# Arduino-Pro-v16.net
KiCad netlist of a schematic drawn in EAGLE
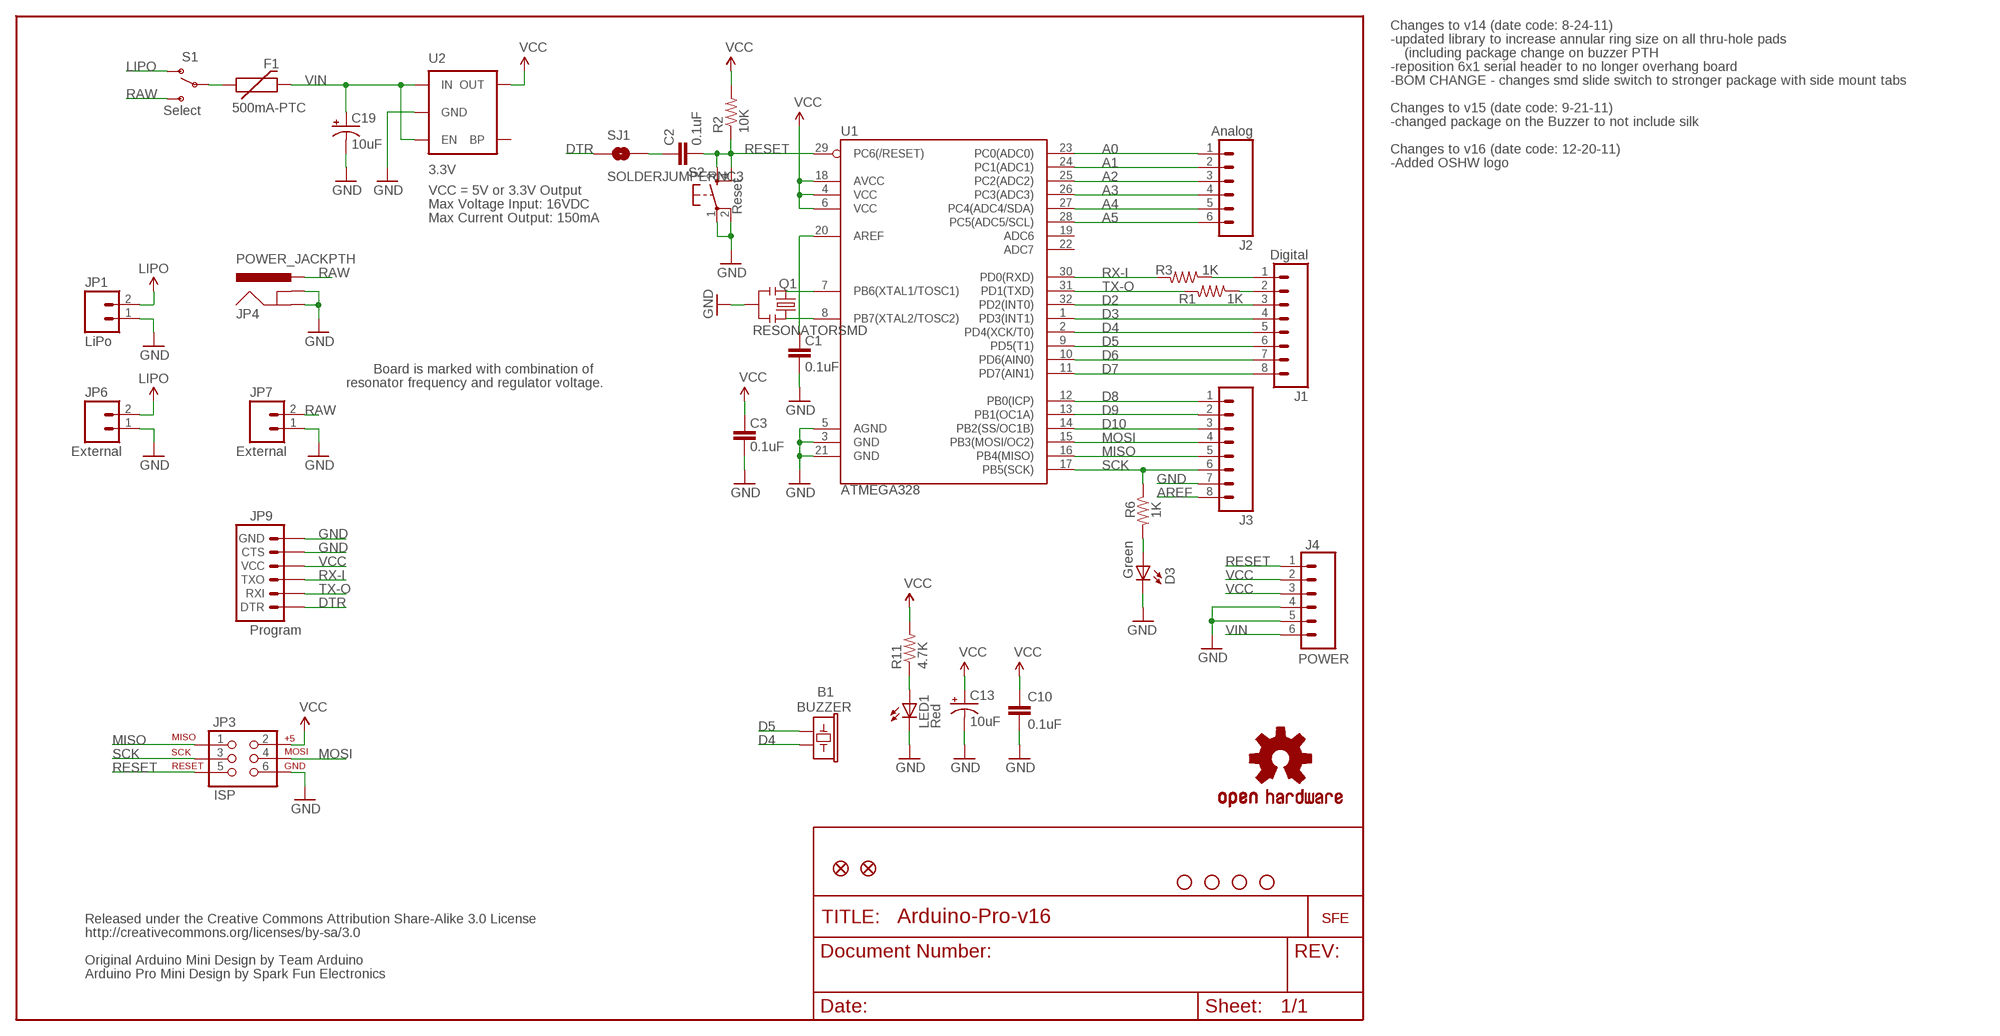
[diagram p0: schematic, sheet 1]

(export (version "E")
  (design (tool "Eeschema 10.0.6"))
  (components
    (comp (ref "B1")
      (value "BUZZER")
      (footprint "eagle-import:BUZZER-12MM-NS-KIT")
      (libsource (lib "eagle-import") (part "BUZZERPTH-NS-KIT"))
    )
    (comp (ref "C1")
      (value "0.1uF")
      (footprint "eagle-import:0402-CAP")
      (libsource (lib "eagle-import") (part "CAP0402-CAP"))
    )
    (comp (ref "C2")
      (value "0.1uF")
      (footprint "eagle-import:0402-CAP")
      (libsource (lib "eagle-import") (part "CAP0402-CAP"))
    )
    (comp (ref "C3")
      (value "0.1uF")
      (footprint "eagle-import:0402-CAP")
      (libsource (lib "eagle-import") (part "CAP0402-CAP"))
    )
    (comp (ref "C10")
      (value "0.1uF")
      (footprint "eagle-import:0402-CAP")
      (libsource (lib "eagle-import") (part "CAP0402-CAP"))
    )
    (comp (ref "C13")
      (value "10uF")
      (footprint "eagle-import:EIA3216")
      (libsource (lib "eagle-import") (part "CAP_POL1206"))
    )
    (comp (ref "C19")
      (value "10uF")
      (footprint "eagle-import:EIA3216")
      (libsource (lib "eagle-import") (part "CAP_POL1206"))
    )
    (comp (ref "D3")
      (value "Green")
      (footprint "eagle-import:LED-0603")
      (libsource (lib "eagle-import") (part "LED0603"))
    )
    (comp (ref "F1")
      (value "500mA-PTC")
      (footprint "eagle-import:PTC-1206")
      (libsource (lib "eagle-import") (part "PTCSMD"))
    )
    (comp (ref "J1")
      (value "Digital")
      (footprint "eagle-import:1X08")
      (libsource (lib "eagle-import") (part "M081X08"))
    )
    (comp (ref "J2")
      (value "Analog")
      (footprint "eagle-import:1X06")
      (libsource (lib "eagle-import") (part "M06SIP"))
    )
    (comp (ref "J3")
      (value "M081X08")
      (footprint "eagle-import:1X08")
      (libsource (lib "eagle-import") (part "M081X08"))
    )
    (comp (ref "J4")
      (value "POWER")
      (footprint "eagle-import:1X06")
      (libsource (lib "eagle-import") (part "M06SIP"))
    )
    (comp (ref "JP1")
      (value "LiPo")
      (footprint "eagle-import:JST-2-SMD")
      (libsource (lib "eagle-import") (part "M02-JST-2MM-SMT"))
    )
    (comp (ref "JP2")
      (value "FIDUCIAL1X2.5")
      (footprint "eagle-import:FIDUCIAL-1X2.5")
      (libsource (lib "eagle-import") (part "FIDUCIAL1X2.5"))
    )
    (comp (ref "JP3")
      (value "ISP")
      (footprint "eagle-import:2X3")
      (libsource (lib "eagle-import") (part "AVR_SPI_PRG_6PTH"))
    )
    (comp (ref "JP4")
      (value "POWER_JACKPTH")
      (footprint "eagle-import:POWER_JACK_PTH")
      (libsource (lib "eagle-import") (part "POWER_JACKPTH"))
    )
    (comp (ref "JP5")
      (value "FIDUCIAL1X2.5")
      (footprint "eagle-import:FIDUCIAL-1X2.5")
      (libsource (lib "eagle-import") (part "FIDUCIAL1X2.5"))
    )
    (comp (ref "JP6")
      (value "External")
      (footprint "eagle-import:1X02")
      (libsource (lib "eagle-import") (part "M02PTH"))
    )
    (comp (ref "JP7")
      (value "External")
      (footprint "eagle-import:1X02")
      (libsource (lib "eagle-import") (part "M02PTH"))
    )
    (comp (ref "JP9")
      (value "Program")
      (footprint "eagle-import:1X06-SMD")
      (libsource (lib "eagle-import") (part "ARDUINO_SERIAL_PROGRAMSMD"))
    )
    (comp (ref "LED1")
      (value "Red")
      (footprint "eagle-import:LED-0603")
      (libsource (lib "eagle-import") (part "LED0603"))
    )
    (comp (ref "Q1")
      (value "RESONATORSMD")
      (footprint "eagle-import:RESONATOR-SMD")
      (libsource (lib "eagle-import") (part "RESONATORSMD"))
    )
    (comp (ref "R1")
      (value "1K")
      (footprint "eagle-import:0402-RES")
      (libsource (lib "eagle-import") (part "RESISTOR0402-RES"))
    )
    (comp (ref "R2")
      (value "10K")
      (footprint "eagle-import:0402-RES")
      (libsource (lib "eagle-import") (part "RESISTOR0402-RES"))
    )
    (comp (ref "R3")
      (value "1K")
      (footprint "eagle-import:0402-RES")
      (libsource (lib "eagle-import") (part "RESISTOR0402-RES"))
    )
    (comp (ref "R6")
      (value "1K")
      (footprint "eagle-import:0402-RES")
      (libsource (lib "eagle-import") (part "RESISTOR0402-RES"))
    )
    (comp (ref "R11")
      (value "4.7K")
      (footprint "eagle-import:0402-RES")
      (libsource (lib "eagle-import") (part "RESISTOR0402-RES"))
    )
    (comp (ref "S1")
      (value "Select")
      (footprint "eagle-import:SWITCH-SPST-SMD-A")
      (libsource (lib "eagle-import") (part "SWITCH-SPST-SMD-A"))
    )
    (comp (ref "S2")
      (value "Reset")
      (footprint "eagle-import:TACTILE_SWITCH_SMD")
      (libsource (lib "eagle-import") (part "TAC_SWITCHSMD"))
    )
    (comp (ref "SJ1")
      (value "SOLDERJUMPERNC3")
      (footprint "eagle-import:SJ_2S-NOTRACE")
      (libsource (lib "eagle-import") (part "SOLDERJUMPERNC2"))
    )
    (comp (ref "U$1")
      (value "STAND-OFF")
      (footprint "eagle-import:STAND-OFF")
      (libsource (lib "eagle-import") (part "STAND-OFF"))
    )
    (comp (ref "U$2")
      (value "OSHW-LOGOL")
      (footprint "eagle-import:OSHW-LOGO-L")
      (libsource (lib "eagle-import") (part "OSHW-LOGOL"))
    )
    (comp (ref "U$3")
      (value "STAND-OFF")
      (footprint "eagle-import:STAND-OFF")
      (libsource (lib "eagle-import") (part "STAND-OFF"))
    )
    (comp (ref "U$9")
      (value "STAND-OFF")
      (footprint "eagle-import:STAND-OFF")
      (libsource (lib "eagle-import") (part "STAND-OFF"))
    )
    (comp (ref "U$10")
      (value "STAND-OFF")
      (footprint "eagle-import:STAND-OFF")
      (libsource (lib "eagle-import") (part "STAND-OFF"))
    )
    (comp (ref "U$11")
      (value "LOGO-SFENEW")
      (footprint "eagle-import:SFE-NEW-WEBLOGO")
      (libsource (lib "eagle-import") (part "LOGO-SFENEW"))
    )
    (comp (ref "U1")
      (value "ATMEGA328")
      (footprint "eagle-import:TQFP32-08")
      (libsource (lib "eagle-import") (part "ATMEGA168"))
    )
    (comp (ref "U2")
      (value "3.3V")
      (footprint "eagle-import:SOT23-5")
      (libsource (lib "eagle-import") (part "V_REG_LDOSMD"))
    )
  )
  (nets
    (net (code "1") (name "/A0") (class "Default")
      (node (ref "J2") (pin "1") (pinfunction "1_1") (pintype "passive"))
      (node (ref "U1") (pin "23") (pinfunction "PC0(ADC0)_23") (pintype "bidirectional"))
    )
    (net (code "2") (name "/A1") (class "Default")
      (node (ref "J2") (pin "2") (pinfunction "2_2") (pintype "passive"))
      (node (ref "U1") (pin "24") (pinfunction "PC1(ADC1)_24") (pintype "bidirectional"))
    )
    (net (code "3") (name "/A2") (class "Default")
      (node (ref "J2") (pin "3") (pinfunction "3_3") (pintype "passive"))
      (node (ref "U1") (pin "25") (pinfunction "PC2(ADC2)_25") (pintype "bidirectional"))
    )
    (net (code "4") (name "/A3") (class "Default")
      (node (ref "J2") (pin "4") (pinfunction "4_4") (pintype "passive"))
      (node (ref "U1") (pin "26") (pinfunction "PC3(ADC3)_26") (pintype "bidirectional"))
    )
    (net (code "5") (name "/A4") (class "Default")
      (node (ref "J2") (pin "5") (pinfunction "5_5") (pintype "passive"))
      (node (ref "U1") (pin "27") (pinfunction "PC4(ADC4/SDA)_27") (pintype "bidirectional"))
    )
    (net (code "6") (name "/A5") (class "Default")
      (node (ref "J2") (pin "6") (pinfunction "6_6") (pintype "passive"))
      (node (ref "U1") (pin "28") (pinfunction "PC5(ADC5/SCL)_28") (pintype "bidirectional"))
    )
    (net (code "7") (name "/AREF") (class "Default")
      (node (ref "C1") (pin "2") (pinfunction "2_2") (pintype "passive"))
      (node (ref "J3") (pin "8") (pinfunction "8_8") (pintype "passive"))
      (node (ref "U1") (pin "20") (pinfunction "AREF_20") (pintype "bidirectional"))
    )
    (net (code "8") (name "/D2") (class "Default")
      (node (ref "J1") (pin "3") (pinfunction "3_3") (pintype "passive"))
      (node (ref "U1") (pin "32") (pinfunction "PD2(INT0)_32") (pintype "bidirectional"))
    )
    (net (code "9") (name "/D3") (class "Default")
      (node (ref "J1") (pin "4") (pinfunction "4_4") (pintype "passive"))
      (node (ref "U1") (pin "1") (pinfunction "PD3(INT1)_1") (pintype "bidirectional"))
    )
    (net (code "10") (name "/D4") (class "Default")
      (node (ref "B1") (pin "-") (pinfunction "2_-") (pintype "passive"))
      (node (ref "J1") (pin "5") (pinfunction "5_5") (pintype "passive"))
      (node (ref "U1") (pin "2") (pinfunction "PD4(XCK/T0)_2") (pintype "bidirectional"))
    )
    (net (code "11") (name "/D5") (class "Default")
      (node (ref "B1") (pin "+") (pinfunction "1_+") (pintype "passive"))
      (node (ref "J1") (pin "6") (pinfunction "6_6") (pintype "passive"))
      (node (ref "U1") (pin "9") (pinfunction "PD5(T1)_9") (pintype "bidirectional"))
    )
    (net (code "12") (name "/D6") (class "Default")
      (node (ref "J1") (pin "7") (pinfunction "7_7") (pintype "passive"))
      (node (ref "U1") (pin "10") (pinfunction "PD6(AIN0)_10") (pintype "bidirectional"))
    )
    (net (code "13") (name "/D7") (class "Default")
      (node (ref "J1") (pin "8") (pinfunction "8_8") (pintype "passive"))
      (node (ref "U1") (pin "11") (pinfunction "PD7(AIN1)_11") (pintype "bidirectional"))
    )
    (net (code "14") (name "/D8") (class "Default")
      (node (ref "J3") (pin "1") (pinfunction "1_1") (pintype "passive"))
      (node (ref "U1") (pin "12") (pinfunction "PB0(ICP)_12") (pintype "bidirectional"))
    )
    (net (code "15") (name "/D9") (class "Default")
      (node (ref "J3") (pin "2") (pinfunction "2_2") (pintype "passive"))
      (node (ref "U1") (pin "13") (pinfunction "PB1(OC1A)_13") (pintype "bidirectional"))
    )
    (net (code "16") (name "/D10") (class "Default")
      (node (ref "J3") (pin "3") (pinfunction "3_3") (pintype "passive"))
      (node (ref "U1") (pin "14") (pinfunction "PB2(SS/OC1B)_14") (pintype "bidirectional"))
    )
    (net (code "17") (name "/DTR") (class "Default")
      (node (ref "JP9") (pin "1") (pinfunction "DTR_1") (pintype "passive"))
      (node (ref "SJ1") (pin "1") (pinfunction "1_1") (pintype "passive"))
    )
    (net (code "18") (name "/MISO") (class "Default")
      (node (ref "J3") (pin "5") (pinfunction "5_5") (pintype "passive"))
      (node (ref "JP3") (pin "1") (pinfunction "1_1") (pintype "passive"))
      (node (ref "U1") (pin "16") (pinfunction "PB4(MISO)_16") (pintype "bidirectional"))
    )
    (net (code "19") (name "/MOSI") (class "Default")
      (node (ref "J3") (pin "4") (pinfunction "4_4") (pintype "passive"))
      (node (ref "JP3") (pin "4") (pinfunction "4_4") (pintype "passive"))
      (node (ref "U1") (pin "15") (pinfunction "PB3(MOSI/OC2)_15") (pintype "bidirectional"))
    )
    (net (code "20") (name "/RAW") (class "Default")
      (node (ref "JP4") (pin "PWR") (pinfunction "PWR_PWR") (pintype "bidirectional"))
      (node (ref "JP7") (pin "2") (pinfunction "2_2") (pintype "passive"))
      (node (ref "S1") (pin "3") (pinfunction "S_3") (pintype "passive"))
    )
    (net (code "21") (name "/RESET") (class "Default")
      (node (ref "C2") (pin "2") (pinfunction "2_2") (pintype "passive"))
      (node (ref "J4") (pin "1") (pinfunction "1_1") (pintype "passive"))
      (node (ref "JP3") (pin "5") (pinfunction "5_5") (pintype "passive"))
      (node (ref "R2") (pin "1") (pinfunction "1_1") (pintype "passive"))
      (node (ref "S2") (pin "3") (pinfunction "3_3") (pintype "passive"))
      (node (ref "S2") (pin "4") (pinfunction "4_4") (pintype "passive"))
      (node (ref "U1") (pin "29") (pinfunction "PC6(/RESET)_29") (pintype "bidirectional"))
    )
    (net (code "22") (name "/RX-I") (class "Default")
      (node (ref "JP9") (pin "3") (pinfunction "TXO_3") (pintype "passive"))
      (node (ref "R3") (pin "2") (pinfunction "2_2") (pintype "passive"))
      (node (ref "U1") (pin "30") (pinfunction "PD0(RXD)_30") (pintype "bidirectional"))
    )
    (net (code "23") (name "/SCK") (class "Default")
      (node (ref "J3") (pin "6") (pinfunction "6_6") (pintype "passive"))
      (node (ref "JP3") (pin "3") (pinfunction "3_3") (pintype "passive"))
      (node (ref "R6") (pin "1") (pinfunction "1_1") (pintype "passive"))
      (node (ref "U1") (pin "17") (pinfunction "PB5(SCK)_17") (pintype "bidirectional"))
    )
    (net (code "24") (name "/TX-O") (class "Default")
      (node (ref "JP9") (pin "2") (pinfunction "RXI_2") (pintype "passive"))
      (node (ref "R1") (pin "2") (pinfunction "2_2") (pintype "passive"))
      (node (ref "U1") (pin "31") (pinfunction "PD1(TXD)_31") (pintype "bidirectional"))
    )
    (net (code "25") (name "/VIN") (class "Default")
      (node (ref "C19") (pin "A") (pinfunction "+_A") (pintype "passive"))
      (node (ref "F1") (pin "2") (pinfunction "2_2") (pintype "bidirectional"))
      (node (ref "J4") (pin "6") (pinfunction "6_6") (pintype "passive"))
      (node (ref "U2") (pin "1") (pinfunction "IN_1") (pintype "input"))
      (node (ref "U2") (pin "3") (pinfunction "EN_3") (pintype "input"))
    )
    (net (code "26") (name "GND") (class "Default")
      (node (ref "C1") (pin "1") (pinfunction "1_1") (pintype "passive"))
      (node (ref "C10") (pin "2") (pinfunction "2_2") (pintype "passive"))
      (node (ref "C13") (pin "C") (pinfunction "-_C") (pintype "passive"))
      (node (ref "C19") (pin "C") (pinfunction "-_C") (pintype "passive"))
      (node (ref "C3") (pin "1") (pinfunction "1_1") (pintype "passive"))
      (node (ref "D3") (pin "C") (pinfunction "C_C") (pintype "passive"))
      (node (ref "J3") (pin "7") (pinfunction "7_7") (pintype "passive"))
      (node (ref "J4") (pin "4") (pinfunction "4_4") (pintype "passive"))
      (node (ref "J4") (pin "5") (pinfunction "5_5") (pintype "passive"))
      (node (ref "JP1") (pin "1") (pinfunction "1_1") (pintype "passive"))
      (node (ref "JP3") (pin "6") (pinfunction "6_6") (pintype "passive"))
      (node (ref "JP4") (pin "GND") (pinfunction "GND_GND") (pintype "bidirectional"))
      (node (ref "JP4") (pin "GNDBREAK") (pinfunction "GNDBREAK_GNDBREAK") (pintype "bidirectional"))
      (node (ref "JP6") (pin "1") (pinfunction "1_1") (pintype "passive"))
      (node (ref "JP7") (pin "1") (pinfunction "1_1") (pintype "passive"))
      (node (ref "JP9") (pin "5") (pinfunction "CTS_5") (pintype "passive"))
      (node (ref "JP9") (pin "6") (pinfunction "GND_6") (pintype "passive"))
      (node (ref "LED1") (pin "C") (pinfunction "C_C") (pintype "passive"))
      (node (ref "Q1") (pin "2") (pinfunction "2_2") (pintype "passive"))
      (node (ref "S2") (pin "1") (pinfunction "1_1") (pintype "passive"))
      (node (ref "S2") (pin "2") (pinfunction "2_2") (pintype "passive"))
      (node (ref "U1") (pin "21") (pinfunction "GND_21") (pintype "bidirectional"))
      (node (ref "U1") (pin "3") (pinfunction "GND_3") (pintype "bidirectional"))
      (node (ref "U1") (pin "5") (pinfunction "AGND_5") (pintype "bidirectional"))
      (node (ref "U2") (pin "2") (pinfunction "GND_2") (pintype "input"))
    )
    (net (code "27") (name "LIPO") (class "Default")
      (node (ref "JP1") (pin "2") (pinfunction "2_2") (pintype "passive"))
      (node (ref "JP6") (pin "2") (pinfunction "2_2") (pintype "passive"))
      (node (ref "S1") (pin "1") (pinfunction "O_1") (pintype "passive"))
    )
    (net (code "28") (name "Net-(C2-Pad1)") (class "Default")
      (node (ref "C2") (pin "1") (pinfunction "1_1") (pintype "passive"))
      (node (ref "SJ1") (pin "2") (pinfunction "2_2") (pintype "passive"))
    )
    (net (code "29") (name "Net-(D3-PadA)") (class "Default")
      (node (ref "D3") (pin "A") (pinfunction "A_A") (pintype "passive"))
      (node (ref "R6") (pin "2") (pinfunction "2_2") (pintype "passive"))
    )
    (net (code "30") (name "Net-(J1-Pad1)") (class "Default")
      (node (ref "J1") (pin "1") (pinfunction "1_1") (pintype "passive"))
      (node (ref "R3") (pin "1") (pinfunction "1_1") (pintype "passive"))
    )
    (net (code "31") (name "Net-(J1-Pad2)") (class "Default")
      (node (ref "J1") (pin "2") (pinfunction "2_2") (pintype "passive"))
      (node (ref "R1") (pin "1") (pinfunction "1_1") (pintype "passive"))
    )
    (net (code "32") (name "Net-(LED1-PadA)") (class "Default")
      (node (ref "LED1") (pin "A") (pinfunction "A_A") (pintype "passive"))
      (node (ref "R11") (pin "1") (pinfunction "1_1") (pintype "passive"))
    )
    (net (code "33") (name "Net-(S1-P)") (class "Default")
      (node (ref "F1") (pin "1") (pinfunction "1_1") (pintype "bidirectional"))
      (node (ref "S1") (pin "2") (pinfunction "P_2") (pintype "passive"))
    )
    (net (code "34") (name "Net-(U1-PB6(XTAL1{slash}TOSC1))") (class "Default")
      (node (ref "Q1") (pin "3") (pinfunction "3_3") (pintype "passive"))
      (node (ref "U1") (pin "7") (pinfunction "PB6(XTAL1/TOSC1)_7") (pintype "bidirectional"))
    )
    (net (code "35") (name "Net-(U1-PB7(XTAL2{slash}TOSC2))") (class "Default")
      (node (ref "Q1") (pin "1") (pinfunction "1_1") (pintype "passive"))
      (node (ref "U1") (pin "8") (pinfunction "PB7(XTAL2/TOSC2)_8") (pintype "bidirectional"))
    )
    (net (code "36") (name "VCC") (class "Default")
      (node (ref "C10") (pin "1") (pinfunction "1_1") (pintype "passive"))
      (node (ref "C13") (pin "A") (pinfunction "+_A") (pintype "passive"))
      (node (ref "C3") (pin "2") (pinfunction "2_2") (pintype "passive"))
      (node (ref "J4") (pin "2") (pinfunction "2_2") (pintype "passive"))
      (node (ref "J4") (pin "3") (pinfunction "3_3") (pintype "passive"))
      (node (ref "JP3") (pin "2") (pinfunction "2_2") (pintype "passive"))
      (node (ref "JP9") (pin "4") (pinfunction "VCC_4") (pintype "passive"))
      (node (ref "R11") (pin "2") (pinfunction "2_2") (pintype "passive"))
      (node (ref "R2") (pin "2") (pinfunction "2_2") (pintype "passive"))
      (node (ref "U1") (pin "18") (pinfunction "AVCC_18") (pintype "bidirectional"))
      (node (ref "U1") (pin "4") (pinfunction "VCC_4") (pintype "bidirectional"))
      (node (ref "U1") (pin "6") (pinfunction "VCC_6") (pintype "bidirectional"))
      (node (ref "U2") (pin "5") (pinfunction "OUT_5") (pintype "passive"))
    )
    (net (code "37") (name "unconnected-(U1-ADC6-Pad19)") (class "Default")
      (node (ref "U1") (pin "19") (pinfunction "ADC6_19") (pintype "bidirectional"))
    )
    (net (code "38") (name "unconnected-(U1-ADC7-Pad22)") (class "Default")
      (node (ref "U1") (pin "22") (pinfunction "ADC7_22") (pintype "bidirectional"))
    )
    (net (code "39") (name "unconnected-(U2-BP-Pad4)") (class "Default")
      (node (ref "U2") (pin "4") (pinfunction "BP_4") (pintype "input"))
    )
  )
)
